# EE_3102.net
KiCad netlist of a schematic drawn in Altium Designer
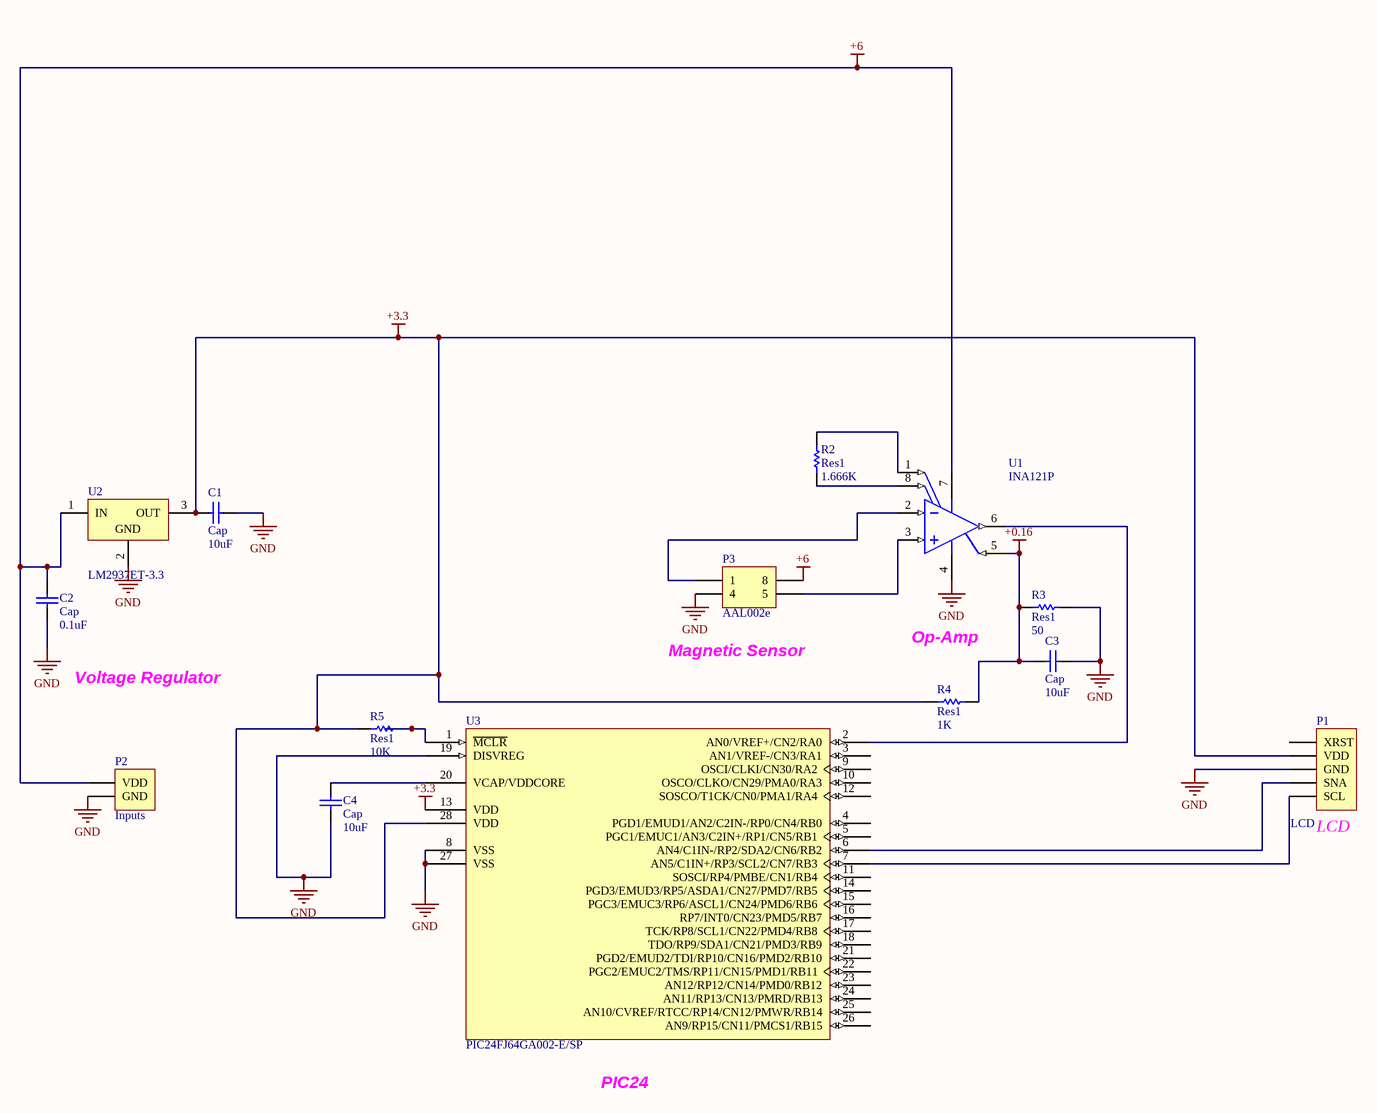
[diagram p0: EE_3102.SchDoc]

(export (version "E")
  (design (tool "Eeschema 10.0.6"))
  (components
    (comp (ref "C1")
      (value "Cap")
      (footprint "RAD-0.3")
      (description "Capacitor")
      (fields (field (name "ALTIUM_VALUE") "10uF") (field (name "PUBLISHER") "Altium Limited"))
      (libsource (lib "Miscellaneous Devices") (part "Cap"))
    )
    (comp (ref "C2")
      (value "Cap")
      (footprint "RAD-0.3")
      (description "Capacitor")
      (fields (field (name "ALTIUM_VALUE") "0.1uF") (field (name "PUBLISHER") "Altium Limited"))
      (libsource (lib "Miscellaneous Devices") (part "Cap"))
    )
    (comp (ref "C3")
      (value "Cap")
      (footprint "RAD-0.3")
      (description "Capacitor")
      (fields (field (name "ALTIUM_VALUE") "10uF") (field (name "PUBLISHER") "Altium Limited"))
      (libsource (lib "Miscellaneous Devices") (part "Cap"))
    )
    (comp (ref "C4")
      (value "Cap")
      (footprint "RAD-0.3")
      (description "Capacitor")
      (fields (field (name "ALTIUM_VALUE") "10uF") (field (name "PUBLISHER") "Altium Limited"))
      (libsource (lib "Miscellaneous Devices") (part "Cap"))
    )
    (comp (ref "P1")
      (value "LCD")
      (footprint "HDR1X5")
      (description "Header, 5-Pin")
      (fields (field (name "PUBLISHER") "Altium Limited"))
      (libsource (lib "Miscellaneous Connectors") (part "Header 5"))
    )
    (comp (ref "P2")
      (value "Inputs")
      (footprint "HDR1X2")
      (description "Header, 2-Pin")
      (fields (field (name "PUBLISHER") "Altium Limited"))
      (libsource (lib "Miscellaneous Connectors") (part "Header 2"))
    )
    (comp (ref "P3")
      (value "AAL002e")
      (footprint "HDR2X2")
      (description "Header, 2-Pin, Dual row")
      (fields (field (name "PUBLISHER") "Altium Limited"))
      (libsource (lib "Miscellaneous Connectors") (part "Header 2X2"))
    )
    (comp (ref "R2")
      (value "Res1")
      (footprint "AXIAL-0.3")
      (description "Resistor")
      (fields (field (name "ALTIUM_VALUE") "1.666K") (field (name "PUBLISHER") "Altium Limited"))
      (libsource (lib "Miscellaneous Devices") (part "Res1"))
    )
    (comp (ref "R3")
      (value "Res1")
      (footprint "AXIAL-0.3")
      (description "Resistor")
      (fields (field (name "ALTIUM_VALUE") "50") (field (name "PUBLISHER") "Altium Limited"))
      (libsource (lib "Miscellaneous Devices") (part "Res1"))
    )
    (comp (ref "R4")
      (value "Res1")
      (footprint "AXIAL-0.3")
      (description "Resistor")
      (fields (field (name "ALTIUM_VALUE") "1K") (field (name "PUBLISHER") "Altium Limited"))
      (libsource (lib "Miscellaneous Devices") (part "Res1"))
    )
    (comp (ref "R5")
      (value "Res1")
      (footprint "AXIAL-0.3")
      (description "Resistor")
      (fields (field (name "ALTIUM_VALUE") "10K") (field (name "PUBLISHER") "Altium Limited"))
      (libsource (lib "Miscellaneous Devices") (part "Res1"))
    )
    (comp (ref "U1")
      (value "INA121P")
      (footprint "P0008A")
      (fields (field (name "MANUFACTURER") "Texas Instruments"))
      (libsource (lib "Altium Content Vault") (part "TI-INA1XX-8"))
    )
    (comp (ref "U2")
      (value "LM2937ET-3.3")
      (footprint "NDE0003A")
      (description "500 mA Low Dropout Regulator, 3-pin TO-220")
      (fields (field (name "MANUFACTURER") "Texas Instruments"))
      (libsource (lib "Altium Content Vault") (part "PM-REG-LM2940-SIL3"))
    )
    (comp (ref "U3")
      (value "PIC24FJ64GA002-E/SP")
      (footprint "SPDIP300-SP28")
      (libsource (lib "Altium Content Vault") (part "MC-16B-16GA002-SOIC28"))
    )
  )
  (nets
    (net (code "1") (name "+0.16") (class "Default")
      (node (ref "C3") (pin "1") (pinfunction "1_1") (pintype "passive"))
      (node (ref "R3") (pin "2") (pinfunction "2_2") (pintype "passive"))
      (node (ref "R4") (pin "1") (pinfunction "1_1") (pintype "passive"))
      (node (ref "U1") (pin "5") (pinfunction "REF_5") (pintype "input"))
    )
    (net (code "2") (name "+3.3") (class "Default")
      (node (ref "C1") (pin "2") (pinfunction "2_2") (pintype "passive"))
      (node (ref "P1") (pin "2") (pinfunction "VDD_2") (pintype "passive"))
      (node (ref "R4") (pin "2") (pinfunction "2_2") (pintype "passive"))
      (node (ref "R5") (pin "1") (pinfunction "1_1") (pintype "passive"))
      (node (ref "U2") (pin "3") (pinfunction "OUT_3") (pintype "power_in"))
      (node (ref "U3") (pin "13") (pinfunction "VDD_13") (pintype "power_in"))
      (node (ref "U3") (pin "28") (pinfunction "VDD_28") (pintype "power_in"))
    )
    (net (code "3") (name "+6") (class "Default")
      (node (ref "C2") (pin "2") (pinfunction "2_2") (pintype "passive"))
      (node (ref "P2") (pin "1") (pinfunction "VDD_1") (pintype "power_in"))
      (node (ref "P3") (pin "2") (pinfunction "8_2") (pintype "passive"))
      (node (ref "U1") (pin "7") (pinfunction "V+_7") (pintype "power_in"))
      (node (ref "U2") (pin "1") (pinfunction "IN_1") (pintype "power_in"))
    )
    (net (code "4") (name "GND") (class "Default")
      (node (ref "C1") (pin "1") (pinfunction "1_1") (pintype "passive"))
      (node (ref "C2") (pin "1") (pinfunction "1_1") (pintype "passive"))
      (node (ref "C3") (pin "2") (pinfunction "2_2") (pintype "passive"))
      (node (ref "C4") (pin "1") (pinfunction "1_1") (pintype "passive"))
      (node (ref "P1") (pin "3") (pinfunction "GND_3") (pintype "passive"))
      (node (ref "P2") (pin "2") (pinfunction "GND_2") (pintype "passive"))
      (node (ref "P3") (pin "3") (pinfunction "4_3") (pintype "passive"))
      (node (ref "R3") (pin "1") (pinfunction "1_1") (pintype "passive"))
      (node (ref "U1") (pin "4") (pinfunction "V-_4") (pintype "power_in"))
      (node (ref "U2") (pin "2") (pinfunction "GND_2") (pintype "power_in"))
      (node (ref "U3") (pin "19") (pinfunction "DISVREG_19") (pintype "input"))
      (node (ref "U3") (pin "27") (pinfunction "VSS_27") (pintype "power_in"))
      (node (ref "U3") (pin "8") (pinfunction "VSS_8") (pintype "power_in"))
    )
    (net (code "5") (name "Net-(P1-SCL)") (class "Default")
      (node (ref "P1") (pin "5") (pinfunction "SCL_5") (pintype "passive"))
      (node (ref "U3") (pin "7") (pinfunction "AN5/C1IN+/RP3/SCL2/CN7/RB3_7") (pintype "bidirectional"))
    )
    (net (code "6") (name "Net-(P1-SNA)") (class "Default")
      (node (ref "P1") (pin "4") (pinfunction "SNA_4") (pintype "passive"))
      (node (ref "U3") (pin "6") (pinfunction "AN4/C1IN-/RP2/SDA2/CN6/RB2_6") (pintype "bidirectional"))
    )
    (net (code "7") (name "Net-(P3-5)") (class "Default")
      (node (ref "P3") (pin "4") (pinfunction "5_4") (pintype "passive"))
      (node (ref "U1") (pin "3") (pinfunction "VIN+_3") (pintype "input"))
    )
    (net (code "8") (name "Net-(R2-Pad1)") (class "Default")
      (node (ref "R2") (pin "1") (pinfunction "1_1") (pintype "passive"))
      (node (ref "U1") (pin "8") (pinfunction "RG_8") (pintype "input"))
    )
    (net (code "9") (name "Net-(R2-Pad2)") (class "Default")
      (node (ref "R2") (pin "2") (pinfunction "2_2") (pintype "passive"))
      (node (ref "U1") (pin "1") (pinfunction "RG_1") (pintype "input"))
    )
    (net (code "10") (name "Net-(U1-VIN-)") (class "Default")
      (node (ref "P3") (pin "1") (pinfunction "1_1") (pintype "passive"))
      (node (ref "U1") (pin "2") (pinfunction "VIN-_2") (pintype "input"))
    )
    (net (code "11") (name "Net-(U1-VO)") (class "Default")
      (node (ref "U1") (pin "6") (pinfunction "VO_6") (pintype "output"))
      (node (ref "U3") (pin "2") (pinfunction "AN0/VREF+/CN2/RA0_2") (pintype "bidirectional"))
    )
    (net (code "12") (name "Net-(U3-VCAP{slash}VDDCORE)") (class "Default")
      (node (ref "C4") (pin "2") (pinfunction "2_2") (pintype "passive"))
      (node (ref "U3") (pin "20") (pinfunction "VCAP/VDDCORE_20") (pintype "power_in"))
    )
    (net (code "13") (name "Net-(U3-~{MCLR})") (class "Default")
      (node (ref "R5") (pin "2") (pinfunction "2_2") (pintype "passive"))
      (node (ref "U3") (pin "1") (pinfunction "~{MCLR}_1") (pintype "input"))
    )
    (net (code "14") (name "unconnected-(P1-XRST-Pad1)") (class "Default")
      (node (ref "P1") (pin "1") (pinfunction "XRST_1") (pintype "passive"))
    )
    (net (code "15") (name "unconnected-(U3-AN1{slash}VREF-{slash}CN3{slash}RA1-Pad3)") (class "Default")
      (node (ref "U3") (pin "3") (pinfunction "AN1/VREF-/CN3/RA1_3") (pintype "bidirectional"))
    )
    (net (code "16") (name "unconnected-(U3-AN9{slash}RP15{slash}CN11{slash}PMCS1{slash}RB15-Pad26)") (class "Default")
      (node (ref "U3") (pin "26") (pinfunction "AN9/RP15/CN11/PMCS1/RB15_26") (pintype "bidirectional"))
    )
    (net (code "17") (name "unconnected-(U3-AN10{slash}CVREF{slash}RTCC{slash}RP14{slash}CN12{slash}PMWR{slash}RB14-Pad25)") (class "Default")
      (node (ref "U3") (pin "25") (pinfunction "AN10/CVREF/RTCC/RP14/CN12/PMWR/RB14_25") (pintype "bidirectional"))
    )
    (net (code "18") (name "unconnected-(U3-AN11{slash}RP13{slash}CN13{slash}PMRD{slash}RB13-Pad24)") (class "Default")
      (node (ref "U3") (pin "24") (pinfunction "AN11/RP13/CN13/PMRD/RB13_24") (pintype "bidirectional"))
    )
    (net (code "19") (name "unconnected-(U3-AN12{slash}RP12{slash}CN14{slash}PMD0{slash}RB12-Pad23)") (class "Default")
      (node (ref "U3") (pin "23") (pinfunction "AN12/RP12/CN14/PMD0/RB12_23") (pintype "bidirectional"))
    )
    (net (code "20") (name "unconnected-(U3-OSCI{slash}CLKI{slash}CN30{slash}RA2-Pad9)") (class "Default")
      (node (ref "U3") (pin "9") (pinfunction "OSCI/CLKI/CN30/RA2_9") (pintype "bidirectional"))
    )
    (net (code "21") (name "unconnected-(U3-OSCO{slash}CLKO{slash}CN29{slash}PMA0{slash}RA3-Pad10)") (class "Default")
      (node (ref "U3") (pin "10") (pinfunction "OSCO/CLKO/CN29/PMA0/RA3_10") (pintype "bidirectional"))
    )
    (net (code "22") (name "unconnected-(U3-PGC1{slash}EMUC1{slash}AN3{slash}C2IN+{slash}RP1{slash}CN5{slash}RB1-Pad5)") (class "Default")
      (node (ref "U3") (pin "5") (pinfunction "PGC1/EMUC1/AN3/C2IN+/RP1/CN5/RB1_5") (pintype "bidirectional"))
    )
    (net (code "23") (name "unconnected-(U3-PGC2{slash}EMUC2{slash}TMS{slash}RP11{slash}CN15{slash}PMD1{slash}RB11-Pad22)") (class "Default")
      (node (ref "U3") (pin "22") (pinfunction "PGC2/EMUC2/TMS/RP11/CN15/PMD1/RB11_22") (pintype "bidirectional"))
    )
    (net (code "24") (name "unconnected-(U3-PGC3{slash}EMUC3{slash}RP6{slash}ASCL1{slash}CN24{slash}PMD6{slash}RB6-Pad15)") (class "Default")
      (node (ref "U3") (pin "15") (pinfunction "PGC3/EMUC3/RP6/ASCL1/CN24/PMD6/RB6_15") (pintype "bidirectional"))
    )
    (net (code "25") (name "unconnected-(U3-PGD1{slash}EMUD1{slash}AN2{slash}C2IN-{slash}RP0{slash}CN4{slash}RB0-Pad4)") (class "Default")
      (node (ref "U3") (pin "4") (pinfunction "PGD1/EMUD1/AN2/C2IN-/RP0/CN4/RB0_4") (pintype "bidirectional"))
    )
    (net (code "26") (name "unconnected-(U3-PGD2{slash}EMUD2{slash}TDI{slash}RP10{slash}CN16{slash}PMD2{slash}RB10-Pad21)") (class "Default")
      (node (ref "U3") (pin "21") (pinfunction "PGD2/EMUD2/TDI/RP10/CN16/PMD2/RB10_21") (pintype "bidirectional"))
    )
    (net (code "27") (name "unconnected-(U3-PGD3{slash}EMUD3{slash}RP5{slash}ASDA1{slash}CN27{slash}PMD7{slash}RB5-Pad14)") (class "Default")
      (node (ref "U3") (pin "14") (pinfunction "PGD3/EMUD3/RP5/ASDA1/CN27/PMD7/RB5_14") (pintype "bidirectional"))
    )
    (net (code "28") (name "unconnected-(U3-RP7{slash}INT0{slash}CN23{slash}PMD5{slash}RB7-Pad16)") (class "Default")
      (node (ref "U3") (pin "16") (pinfunction "RP7/INT0/CN23/PMD5/RB7_16") (pintype "bidirectional"))
    )
    (net (code "29") (name "unconnected-(U3-SOSCI{slash}RP4{slash}PMBE{slash}CN1{slash}RB4-Pad11)") (class "Default")
      (node (ref "U3") (pin "11") (pinfunction "SOSCI/RP4/PMBE/CN1/RB4_11") (pintype "bidirectional"))
    )
    (net (code "30") (name "unconnected-(U3-SOSCO{slash}T1CK{slash}CN0{slash}PMA1{slash}RA4-Pad12)") (class "Default")
      (node (ref "U3") (pin "12") (pinfunction "SOSCO/T1CK/CN0/PMA1/RA4_12") (pintype "bidirectional"))
    )
    (net (code "31") (name "unconnected-(U3-TCK{slash}RP8{slash}SCL1{slash}CN22{slash}PMD4{slash}RB8-Pad17)") (class "Default")
      (node (ref "U3") (pin "17") (pinfunction "TCK/RP8/SCL1/CN22/PMD4/RB8_17") (pintype "bidirectional"))
    )
    (net (code "32") (name "unconnected-(U3-TDO{slash}RP9{slash}SDA1{slash}CN21{slash}PMD3{slash}RB9-Pad18)") (class "Default")
      (node (ref "U3") (pin "18") (pinfunction "TDO/RP9/SDA1/CN21/PMD3/RB9_18") (pintype "bidirectional"))
    )
  )
)
